# proj_konovalov_motor_driver.net
KiCad netlist of a schematic drawn in Altium Designer
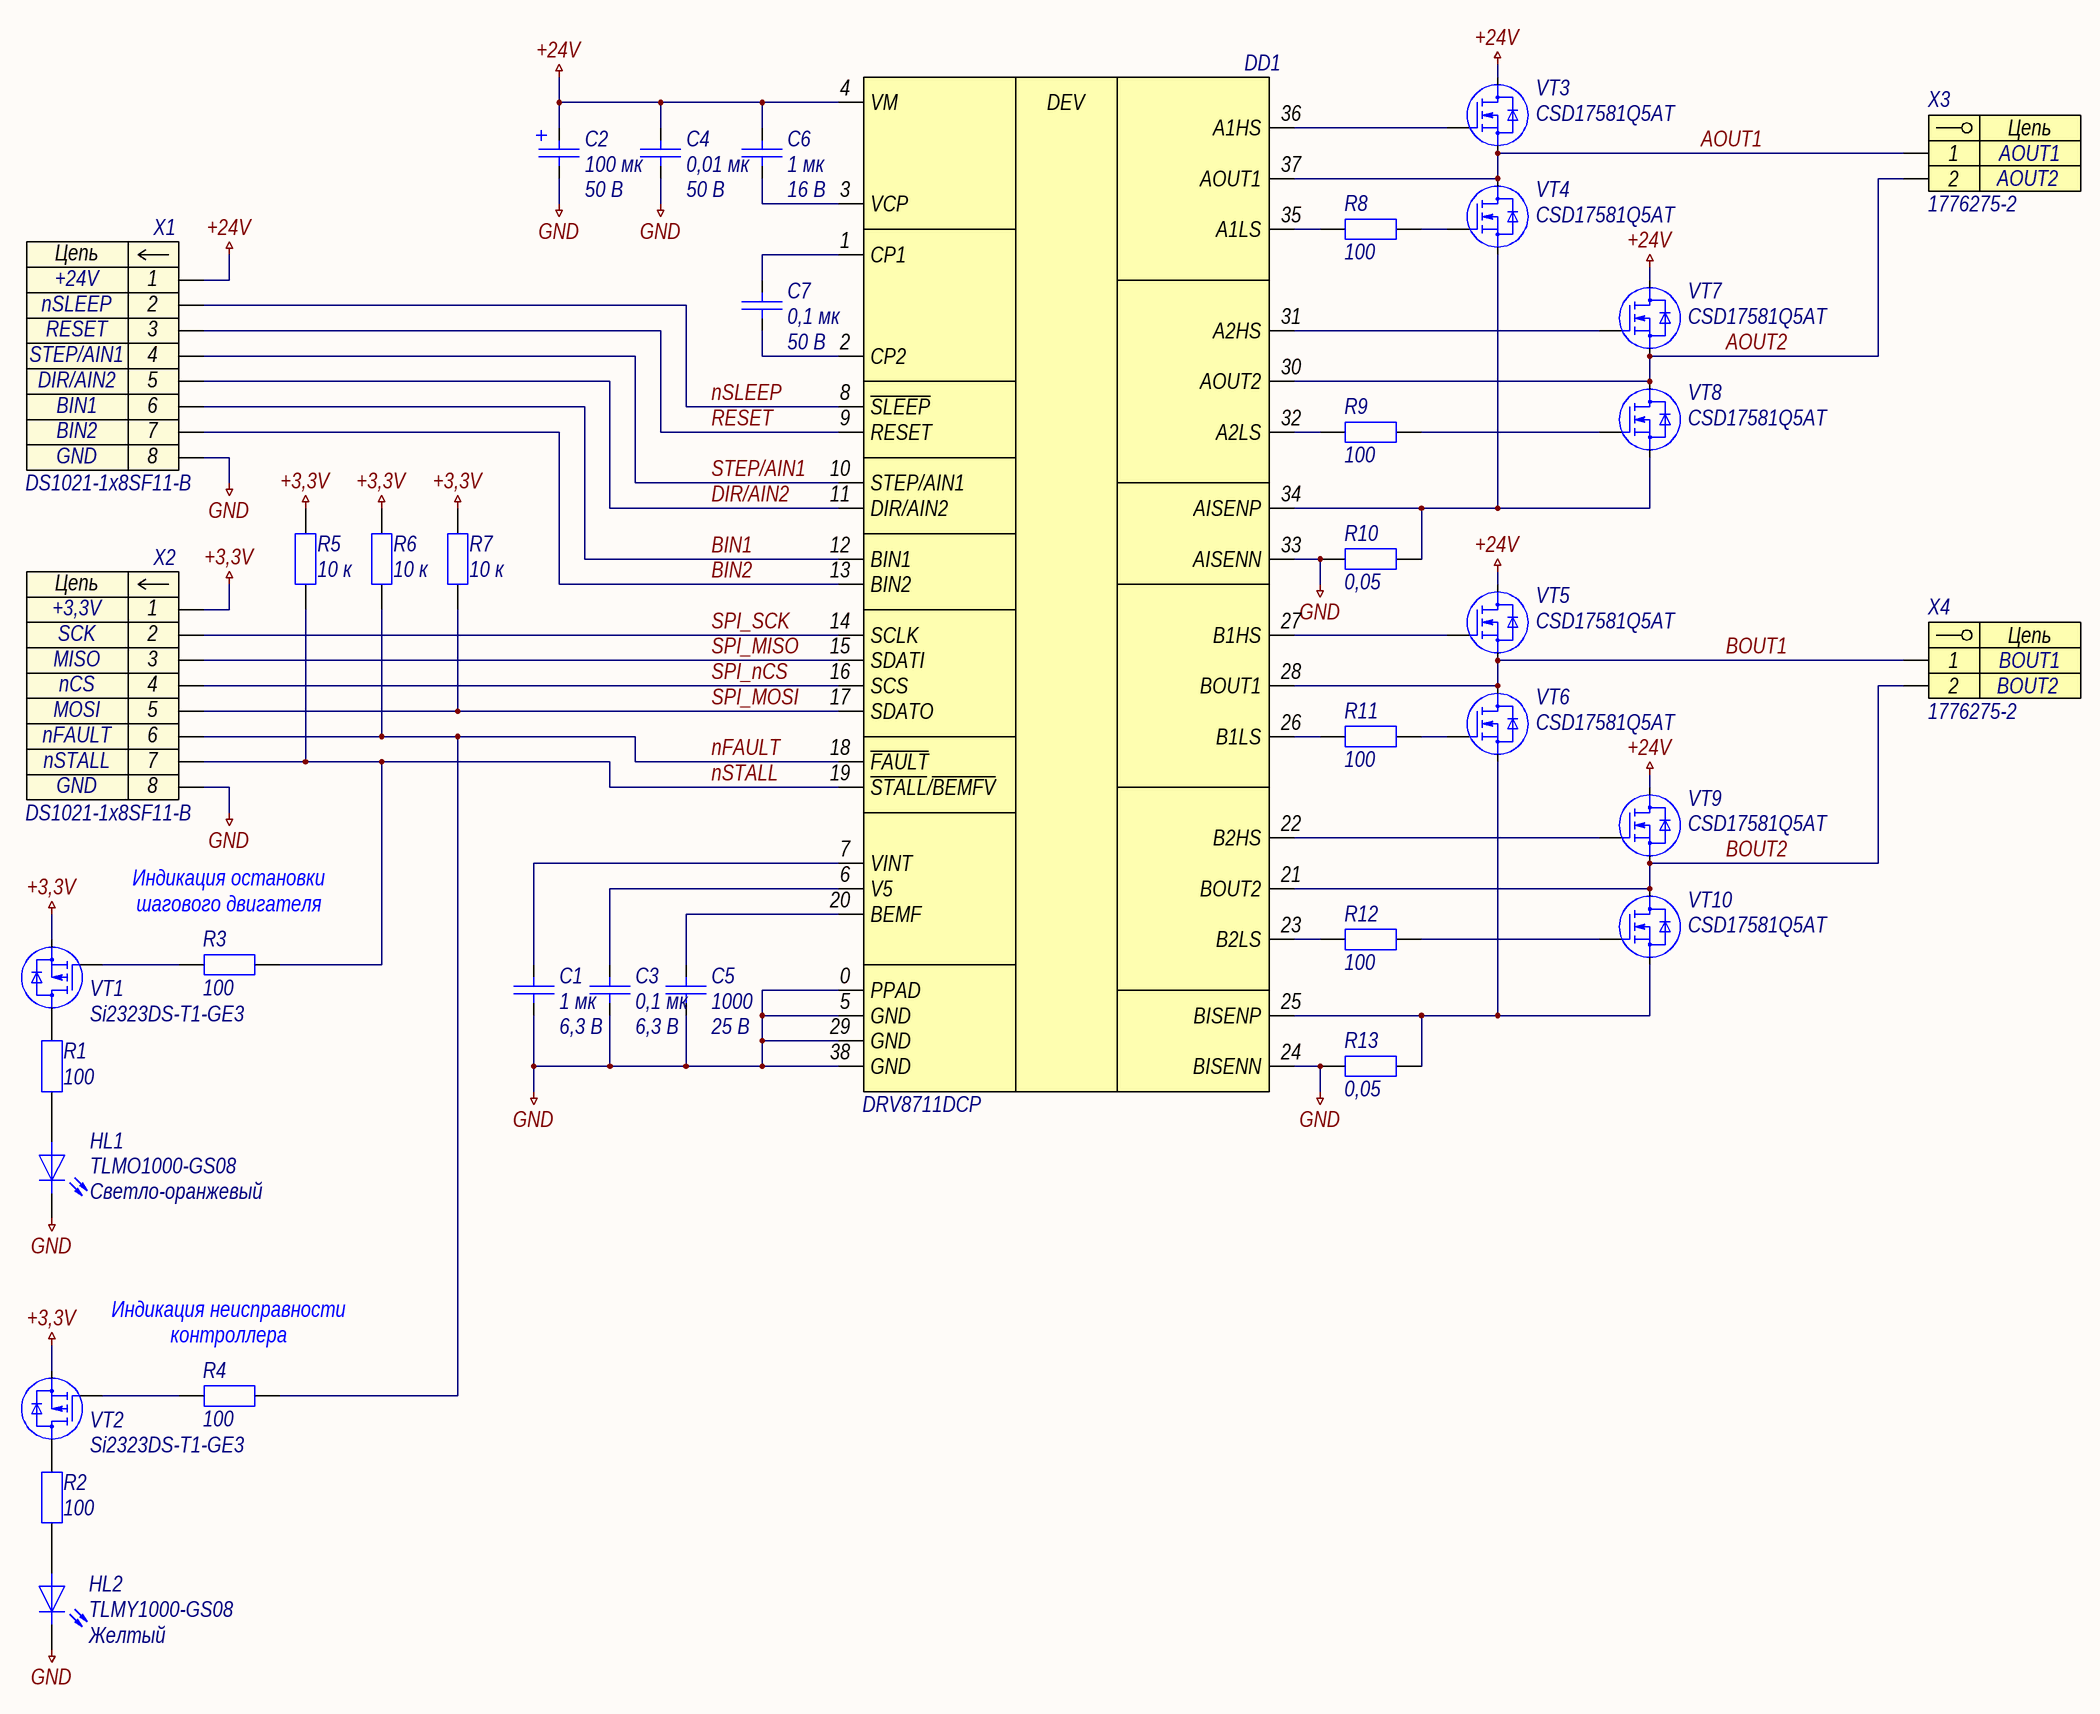
[diagram p0: proj_konovalov_motor_driver.SchDoc]

(export (version "E")
  (design (tool "Eeschema 10.0.6"))
  (components
    (comp (ref "C1")
      (value "1 мк")
      (footprint "C0603")
      (description "=Описание")
      (fields (field (name "НАПРЯЖЕНИЕ") "6,3 В"))
      (libsource (lib "Database_Students") (part "CAPACITOR-NONPOLAR"))
    )
    (comp (ref "C2")
      (value "100 мк")
      (footprint "CAPAE-660X660X800")
      (description "=Описание")
      (fields (field (name "НАПРЯЖЕНИЕ") "50 В"))
      (libsource (lib "Database_Students") (part "CAPACITOR-POLAR"))
    )
    (comp (ref "C3")
      (value "0,1 мк")
      (footprint "C0603")
      (description "=Описание")
      (fields (field (name "НАПРЯЖЕНИЕ") "6,3 В"))
      (libsource (lib "Database_Students") (part "CAPACITOR-NONPOLAR"))
    )
    (comp (ref "C4")
      (value "0,01 мк")
      (footprint "C0603")
      (description "=Описание")
      (fields (field (name "НАПРЯЖЕНИЕ") "50 В"))
      (libsource (lib "Database_Students") (part "CAPACITOR-NONPOLAR"))
    )
    (comp (ref "C5")
      (value "1000")
      (footprint "C0603")
      (description "=Описание")
      (fields (field (name "НАПРЯЖЕНИЕ") "25 В"))
      (libsource (lib "Database_Students") (part "CAPACITOR-NONPOLAR"))
    )
    (comp (ref "C6")
      (value "1 мк")
      (footprint "C0603")
      (description "=Описание")
      (fields (field (name "НАПРЯЖЕНИЕ") "16 В"))
      (libsource (lib "Database_Students") (part "CAPACITOR-NONPOLAR"))
    )
    (comp (ref "C7")
      (value "0,1 мк")
      (footprint "C0603")
      (description "=Описание")
      (fields (field (name "НАПРЯЖЕНИЕ") "50 В"))
      (libsource (lib "Database_Students") (part "CAPACITOR-NONPOLAR"))
    )
    (comp (ref "DD1")
      (value "DRV8711DCP")
      (footprint "HTSSOP-38-P50-470X290X120-L63X22-T470X290")
      (description "=Описание")
      (libsource (lib "Database_Students") (part "DRV8711DCP"))
    )
    (comp (ref "HL1")
      (value "TLMO1000-GS08")
      (footprint "HL0603")
      (description "=Описание")
      (fields (field (name "ЦВЕТ") "Светло-оранжевый"))
      (libsource (lib "Database_Students") (part "LED-COMMON"))
    )
    (comp (ref "HL2")
      (value "TLMY1000-GS08")
      (footprint "HL0603")
      (description "=Описание")
      (fields (field (name "ЦВЕТ") "Желтый"))
      (libsource (lib "Database_Students") (part "LED-COMMON"))
    )
    (comp (ref "R1")
      (value "100")
      (footprint "R0603")
      (description "=Описание")
      (libsource (lib "Database_Students") (part "RESISTOR-COMMON"))
    )
    (comp (ref "R2")
      (value "100")
      (footprint "R0603")
      (description "=Описание")
      (libsource (lib "Database_Students") (part "RESISTOR-COMMON"))
    )
    (comp (ref "R3")
      (value "100")
      (footprint "R0603")
      (description "=Описание")
      (libsource (lib "Database_Students") (part "RESISTOR-COMMON"))
    )
    (comp (ref "R4")
      (value "100")
      (footprint "R0603")
      (description "=Описание")
      (libsource (lib "Database_Students") (part "RESISTOR-COMMON"))
    )
    (comp (ref "R5")
      (value "10 к")
      (footprint "R0603")
      (description "=Описание")
      (libsource (lib "Database_Students") (part "RESISTOR-COMMON"))
    )
    (comp (ref "R6")
      (value "10 к")
      (footprint "R0603")
      (description "=Описание")
      (libsource (lib "Database_Students") (part "RESISTOR-COMMON"))
    )
    (comp (ref "R7")
      (value "10 к")
      (footprint "R0603")
      (description "=Описание")
      (libsource (lib "Database_Students") (part "RESISTOR-COMMON"))
    )
    (comp (ref "R8")
      (value "100")
      (footprint "R0603")
      (description "=Описание")
      (libsource (lib "Database_Students") (part "RESISTOR-COMMON"))
    )
    (comp (ref "R9")
      (value "100")
      (footprint "R0603")
      (description "=Описание")
      (libsource (lib "Database_Students") (part "RESISTOR-COMMON"))
    )
    (comp (ref "R10")
      (value "0,05")
      (footprint "R0603")
      (description "=Описание")
      (libsource (lib "Database_Students") (part "RESISTOR-COMMON"))
    )
    (comp (ref "R11")
      (value "100")
      (footprint "R0603")
      (description "=Описание")
      (libsource (lib "Database_Students") (part "RESISTOR-COMMON"))
    )
    (comp (ref "R12")
      (value "100")
      (footprint "R0603")
      (description "=Описание")
      (libsource (lib "Database_Students") (part "RESISTOR-COMMON"))
    )
    (comp (ref "R13")
      (value "0,05")
      (footprint "R0603")
      (description "=Описание")
      (libsource (lib "Database_Students") (part "RESISTOR-COMMON"))
    )
    (comp (ref "VT1")
      (value "Si2323DS-T1-GE3")
      (footprint "SOT-23-3-P95-292X237X112")
      (description "=Описание")
      (libsource (lib "Database_Students") (part "MOSFET-P-DIODE"))
    )
    (comp (ref "VT2")
      (value "Si2323DS-T1-GE3")
      (footprint "SOT-23-3-P95-292X237X112")
      (description "=Описание")
      (libsource (lib "Database_Students") (part "MOSFET-P-DIODE"))
    )
    (comp (ref "VT3")
      (value "CSD17581Q5AT")
      (footprint "VSONP-8-P127-600X500X110")
      (description "=Описание")
      (libsource (lib "Database_Students") (part "MOSFET-N-DIODE"))
    )
    (comp (ref "VT4")
      (value "CSD17581Q5AT")
      (footprint "VSONP-8-P127-600X500X110")
      (description "=Описание")
      (libsource (lib "Database_Students") (part "MOSFET-N-DIODE"))
    )
    (comp (ref "VT5")
      (value "CSD17581Q5AT")
      (footprint "VSONP-8-P127-600X500X110")
      (description "=Описание")
      (libsource (lib "Database_Students") (part "MOSFET-N-DIODE"))
    )
    (comp (ref "VT6")
      (value "CSD17581Q5AT")
      (footprint "VSONP-8-P127-600X500X110")
      (description "=Описание")
      (libsource (lib "Database_Students") (part "MOSFET-N-DIODE"))
    )
    (comp (ref "VT7")
      (value "CSD17581Q5AT")
      (footprint "VSONP-8-P127-600X500X110")
      (description "=Описание")
      (libsource (lib "Database_Students") (part "MOSFET-N-DIODE"))
    )
    (comp (ref "VT8")
      (value "CSD17581Q5AT")
      (footprint "VSONP-8-P127-600X500X110")
      (description "=Описание")
      (libsource (lib "Database_Students") (part "MOSFET-N-DIODE"))
    )
    (comp (ref "VT9")
      (value "CSD17581Q5AT")
      (footprint "VSONP-8-P127-600X500X110")
      (description "=Описание")
      (libsource (lib "Database_Students") (part "MOSFET-N-DIODE"))
    )
    (comp (ref "VT10")
      (value "CSD17581Q5AT")
      (footprint "VSONP-8-P127-600X500X110")
      (description "=Описание")
      (libsource (lib "Database_Students") (part "MOSFET-N-DIODE"))
    )
    (comp (ref "X1")
      (value "DS1021-1x8SF11-B")
      (footprint "DS1021-1X8SF11-B")
      (description "=Описание")
      (libsource (lib "Database_Students") (part "HEADER-8-PLG"))
    )
    (comp (ref "X2")
      (value "DS1021-1x8SF11-B")
      (footprint "DS1021-1X8SF11-B")
      (description "=Описание")
      (libsource (lib "Database_Students") (part "HEADER-8-PLG"))
    )
    (comp (ref "X3")
      (value "1776275-2")
      (footprint "1776275-2")
      (description "=Описание")
      (libsource (lib "Database_Students") (part "HEADER-2-TRM"))
    )
    (comp (ref "X4")
      (value "1776275-2")
      (footprint "1776275-2")
      (description "=Описание")
      (libsource (lib "Database_Students") (part "HEADER-2-TRM"))
    )
  )
  (nets
    (net (code "1") (name "+3,3V") (class "Default")
      (node (ref "R5") (pin "2") (pinfunction "2_2") (pintype "passive"))
      (node (ref "R6") (pin "2") (pinfunction "2_2") (pintype "passive"))
      (node (ref "R7") (pin "2") (pinfunction "2_2") (pintype "passive"))
      (node (ref "VT1") (pin "S") (pinfunction "S_S") (pintype "passive"))
      (node (ref "VT2") (pin "S") (pinfunction "S_S") (pintype "passive"))
      (node (ref "X2") (pin "1") (pinfunction "1_1") (pintype "passive"))
    )
    (net (code "2") (name "+24V") (class "Default")
      (node (ref "C2") (pin "1") (pinfunction "1_1") (pintype "passive"))
      (node (ref "C4") (pin "1") (pinfunction "1_1") (pintype "passive"))
      (node (ref "C6") (pin "1") (pinfunction "1_1") (pintype "passive"))
      (node (ref "DD1") (pin "4") (pinfunction "VM_4") (pintype "passive"))
      (node (ref "VT3") (pin "D") (pinfunction "D_D") (pintype "passive"))
      (node (ref "VT5") (pin "D") (pinfunction "D_D") (pintype "passive"))
      (node (ref "VT7") (pin "D") (pinfunction "D_D") (pintype "passive"))
      (node (ref "VT9") (pin "D") (pinfunction "D_D") (pintype "passive"))
      (node (ref "X1") (pin "1") (pinfunction "1_1") (pintype "passive"))
    )
    (net (code "3") (name "/AOUT1") (class "Default")
      (node (ref "DD1") (pin "37") (pinfunction "AOUT1_37") (pintype "passive"))
      (node (ref "VT3") (pin "S") (pinfunction "S_S") (pintype "passive"))
      (node (ref "VT4") (pin "D") (pinfunction "D_D") (pintype "passive"))
      (node (ref "X3") (pin "1") (pinfunction "1_1") (pintype "passive"))
    )
    (net (code "4") (name "/AOUT2") (class "Default")
      (node (ref "DD1") (pin "30") (pinfunction "AOUT2_30") (pintype "passive"))
      (node (ref "VT7") (pin "S") (pinfunction "S_S") (pintype "passive"))
      (node (ref "VT8") (pin "D") (pinfunction "D_D") (pintype "passive"))
      (node (ref "X3") (pin "2") (pinfunction "2_2") (pintype "passive"))
    )
    (net (code "5") (name "/BIN1") (class "Default")
      (node (ref "DD1") (pin "12") (pinfunction "BIN1_12") (pintype "passive"))
      (node (ref "X1") (pin "6") (pinfunction "6_6") (pintype "passive"))
    )
    (net (code "6") (name "/BIN2") (class "Default")
      (node (ref "DD1") (pin "13") (pinfunction "BIN2_13") (pintype "passive"))
      (node (ref "X1") (pin "7") (pinfunction "7_7") (pintype "passive"))
    )
    (net (code "7") (name "/BOUT1") (class "Default")
      (node (ref "DD1") (pin "28") (pinfunction "BOUT1_28") (pintype "passive"))
      (node (ref "VT5") (pin "S") (pinfunction "S_S") (pintype "passive"))
      (node (ref "VT6") (pin "D") (pinfunction "D_D") (pintype "passive"))
      (node (ref "X4") (pin "1") (pinfunction "1_1") (pintype "passive"))
    )
    (net (code "8") (name "/BOUT2") (class "Default")
      (node (ref "DD1") (pin "21") (pinfunction "BOUT2_21") (pintype "passive"))
      (node (ref "VT10") (pin "D") (pinfunction "D_D") (pintype "passive"))
      (node (ref "VT9") (pin "S") (pinfunction "S_S") (pintype "passive"))
      (node (ref "X4") (pin "2") (pinfunction "2_2") (pintype "passive"))
    )
    (net (code "9") (name "/DIR{slash}AIN2") (class "Default")
      (node (ref "DD1") (pin "11") (pinfunction "DIR/AIN2_11") (pintype "passive"))
      (node (ref "X1") (pin "5") (pinfunction "5_5") (pintype "passive"))
    )
    (net (code "10") (name "/RESET") (class "Default")
      (node (ref "DD1") (pin "9") (pinfunction "RESET_9") (pintype "passive"))
      (node (ref "X1") (pin "3") (pinfunction "3_3") (pintype "passive"))
    )
    (net (code "11") (name "/SPI_MISO") (class "Default")
      (node (ref "DD1") (pin "15") (pinfunction "SDATI_15") (pintype "passive"))
      (node (ref "X2") (pin "3") (pinfunction "3_3") (pintype "passive"))
    )
    (net (code "12") (name "/SPI_MOSI") (class "Default")
      (node (ref "DD1") (pin "17") (pinfunction "SDATO_17") (pintype "passive"))
      (node (ref "R7") (pin "1") (pinfunction "1_1") (pintype "passive"))
      (node (ref "X2") (pin "5") (pinfunction "5_5") (pintype "passive"))
    )
    (net (code "13") (name "/SPI_SCK") (class "Default")
      (node (ref "DD1") (pin "14") (pinfunction "SCLK_14") (pintype "passive"))
      (node (ref "X2") (pin "2") (pinfunction "2_2") (pintype "passive"))
    )
    (net (code "14") (name "/SPI_nCS") (class "Default")
      (node (ref "DD1") (pin "16") (pinfunction "SCS_16") (pintype "passive"))
      (node (ref "X2") (pin "4") (pinfunction "4_4") (pintype "passive"))
    )
    (net (code "15") (name "/STEP{slash}AIN1") (class "Default")
      (node (ref "DD1") (pin "10") (pinfunction "STEP/AIN1_10") (pintype "passive"))
      (node (ref "X1") (pin "4") (pinfunction "4_4") (pintype "passive"))
    )
    (net (code "16") (name "/nFAULT") (class "Default")
      (node (ref "DD1") (pin "18") (pinfunction "~{FAULT}_18") (pintype "passive"))
      (node (ref "R4") (pin "2") (pinfunction "2_2") (pintype "passive"))
      (node (ref "R6") (pin "1") (pinfunction "1_1") (pintype "passive"))
      (node (ref "X2") (pin "6") (pinfunction "6_6") (pintype "passive"))
    )
    (net (code "17") (name "/nSLEEP") (class "Default")
      (node (ref "DD1") (pin "8") (pinfunction "~{SLEEP}_8") (pintype "passive"))
      (node (ref "X1") (pin "2") (pinfunction "2_2") (pintype "passive"))
    )
    (net (code "18") (name "/nSTALL") (class "Default")
      (node (ref "DD1") (pin "19") (pinfunction "~{STALL}/~{BEMFV}_19") (pintype "passive"))
      (node (ref "R3") (pin "2") (pinfunction "2_2") (pintype "passive"))
      (node (ref "R5") (pin "1") (pinfunction "1_1") (pintype "passive"))
      (node (ref "X2") (pin "7") (pinfunction "7_7") (pintype "passive"))
    )
    (net (code "19") (name "GND") (class "Default")
      (node (ref "C1") (pin "2") (pinfunction "2_2") (pintype "passive"))
      (node (ref "C2") (pin "2") (pinfunction "2_2") (pintype "passive"))
      (node (ref "C3") (pin "2") (pinfunction "2_2") (pintype "passive"))
      (node (ref "C4") (pin "2") (pinfunction "2_2") (pintype "passive"))
      (node (ref "C5") (pin "2") (pinfunction "2_2") (pintype "passive"))
      (node (ref "DD1") (pin "0") (pinfunction "PPAD_0") (pintype "passive"))
      (node (ref "DD1") (pin "24") (pinfunction "BISENN_24") (pintype "passive"))
      (node (ref "DD1") (pin "29") (pinfunction "GND_29") (pintype "passive"))
      (node (ref "DD1") (pin "33") (pinfunction "AISENN_33") (pintype "passive"))
      (node (ref "DD1") (pin "38") (pinfunction "GND_38") (pintype "passive"))
      (node (ref "DD1") (pin "5") (pinfunction "GND_5") (pintype "passive"))
      (node (ref "HL1") (pin "1") (pinfunction "1_1") (pintype "passive"))
      (node (ref "HL2") (pin "1") (pinfunction "1_1") (pintype "passive"))
      (node (ref "R10") (pin "1") (pinfunction "1_1") (pintype "passive"))
      (node (ref "R13") (pin "1") (pinfunction "1_1") (pintype "passive"))
      (node (ref "X1") (pin "8") (pinfunction "8_8") (pintype "passive"))
      (node (ref "X2") (pin "8") (pinfunction "8_8") (pintype "passive"))
    )
    (net (code "20") (name "Net-(DD1-A1HS)") (class "Default")
      (node (ref "DD1") (pin "36") (pinfunction "A1HS_36") (pintype "passive"))
      (node (ref "VT3") (pin "G") (pinfunction "G_G") (pintype "passive"))
    )
    (net (code "21") (name "Net-(DD1-A1LS)") (class "Default")
      (node (ref "DD1") (pin "35") (pinfunction "A1LS_35") (pintype "passive"))
      (node (ref "R8") (pin "1") (pinfunction "1_1") (pintype "passive"))
    )
    (net (code "22") (name "Net-(DD1-A2HS)") (class "Default")
      (node (ref "DD1") (pin "31") (pinfunction "A2HS_31") (pintype "passive"))
      (node (ref "VT7") (pin "G") (pinfunction "G_G") (pintype "passive"))
    )
    (net (code "23") (name "Net-(DD1-A2LS)") (class "Default")
      (node (ref "DD1") (pin "32") (pinfunction "A2LS_32") (pintype "passive"))
      (node (ref "R9") (pin "1") (pinfunction "1_1") (pintype "passive"))
    )
    (net (code "24") (name "Net-(DD1-AISENP)") (class "Default")
      (node (ref "DD1") (pin "34") (pinfunction "AISENP_34") (pintype "passive"))
      (node (ref "R10") (pin "2") (pinfunction "2_2") (pintype "passive"))
      (node (ref "VT4") (pin "S") (pinfunction "S_S") (pintype "passive"))
      (node (ref "VT8") (pin "S") (pinfunction "S_S") (pintype "passive"))
    )
    (net (code "25") (name "Net-(DD1-B1HS)") (class "Default")
      (node (ref "DD1") (pin "27") (pinfunction "B1HS_27") (pintype "passive"))
      (node (ref "VT5") (pin "G") (pinfunction "G_G") (pintype "passive"))
    )
    (net (code "26") (name "Net-(DD1-B1LS)") (class "Default")
      (node (ref "DD1") (pin "26") (pinfunction "B1LS_26") (pintype "passive"))
      (node (ref "R11") (pin "1") (pinfunction "1_1") (pintype "passive"))
    )
    (net (code "27") (name "Net-(DD1-B2HS)") (class "Default")
      (node (ref "DD1") (pin "22") (pinfunction "B2HS_22") (pintype "passive"))
      (node (ref "VT9") (pin "G") (pinfunction "G_G") (pintype "passive"))
    )
    (net (code "28") (name "Net-(DD1-B2LS)") (class "Default")
      (node (ref "DD1") (pin "23") (pinfunction "B2LS_23") (pintype "passive"))
      (node (ref "R12") (pin "1") (pinfunction "1_1") (pintype "passive"))
    )
    (net (code "29") (name "Net-(DD1-BEMF)") (class "Default")
      (node (ref "C5") (pin "1") (pinfunction "1_1") (pintype "passive"))
      (node (ref "DD1") (pin "20") (pinfunction "BEMF_20") (pintype "passive"))
    )
    (net (code "30") (name "Net-(DD1-BISENP)") (class "Default")
      (node (ref "DD1") (pin "25") (pinfunction "BISENP_25") (pintype "passive"))
      (node (ref "R13") (pin "2") (pinfunction "2_2") (pintype "passive"))
      (node (ref "VT10") (pin "S") (pinfunction "S_S") (pintype "passive"))
      (node (ref "VT6") (pin "S") (pinfunction "S_S") (pintype "passive"))
    )
    (net (code "31") (name "Net-(DD1-CP1)") (class "Default")
      (node (ref "C7") (pin "1") (pinfunction "1_1") (pintype "passive"))
      (node (ref "DD1") (pin "1") (pinfunction "CP1_1") (pintype "passive"))
    )
    (net (code "32") (name "Net-(DD1-CP2)") (class "Default")
      (node (ref "C7") (pin "2") (pinfunction "2_2") (pintype "passive"))
      (node (ref "DD1") (pin "2") (pinfunction "CP2_2") (pintype "passive"))
    )
    (net (code "33") (name "Net-(DD1-V5)") (class "Default")
      (node (ref "C3") (pin "1") (pinfunction "1_1") (pintype "passive"))
      (node (ref "DD1") (pin "6") (pinfunction "V5_6") (pintype "passive"))
    )
    (net (code "34") (name "Net-(DD1-VCP)") (class "Default")
      (node (ref "C6") (pin "2") (pinfunction "2_2") (pintype "passive"))
      (node (ref "DD1") (pin "3") (pinfunction "VCP_3") (pintype "passive"))
    )
    (net (code "35") (name "Net-(DD1-VINT)") (class "Default")
      (node (ref "C1") (pin "1") (pinfunction "1_1") (pintype "passive"))
      (node (ref "DD1") (pin "7") (pinfunction "VINT_7") (pintype "passive"))
    )
    (net (code "36") (name "Net-(HL1-Pad2)") (class "Default")
      (node (ref "HL1") (pin "2") (pinfunction "2_2") (pintype "passive"))
      (node (ref "R1") (pin "1") (pinfunction "1_1") (pintype "passive"))
    )
    (net (code "37") (name "Net-(HL2-Pad2)") (class "Default")
      (node (ref "HL2") (pin "2") (pinfunction "2_2") (pintype "passive"))
      (node (ref "R2") (pin "1") (pinfunction "1_1") (pintype "passive"))
    )
    (net (code "38") (name "Net-(R1-Pad2)") (class "Default")
      (node (ref "R1") (pin "2") (pinfunction "2_2") (pintype "passive"))
      (node (ref "VT1") (pin "D") (pinfunction "D_D") (pintype "passive"))
    )
    (net (code "39") (name "Net-(R2-Pad2)") (class "Default")
      (node (ref "R2") (pin "2") (pinfunction "2_2") (pintype "passive"))
      (node (ref "VT2") (pin "D") (pinfunction "D_D") (pintype "passive"))
    )
    (net (code "40") (name "Net-(R3-Pad1)") (class "Default")
      (node (ref "R3") (pin "1") (pinfunction "1_1") (pintype "passive"))
      (node (ref "VT1") (pin "G") (pinfunction "G_G") (pintype "passive"))
    )
    (net (code "41") (name "Net-(R4-Pad1)") (class "Default")
      (node (ref "R4") (pin "1") (pinfunction "1_1") (pintype "passive"))
      (node (ref "VT2") (pin "G") (pinfunction "G_G") (pintype "passive"))
    )
    (net (code "42") (name "Net-(R8-Pad2)") (class "Default")
      (node (ref "R8") (pin "2") (pinfunction "2_2") (pintype "passive"))
      (node (ref "VT4") (pin "G") (pinfunction "G_G") (pintype "passive"))
    )
    (net (code "43") (name "Net-(R9-Pad2)") (class "Default")
      (node (ref "R9") (pin "2") (pinfunction "2_2") (pintype "passive"))
      (node (ref "VT8") (pin "G") (pinfunction "G_G") (pintype "passive"))
    )
    (net (code "44") (name "Net-(R11-Pad2)") (class "Default")
      (node (ref "R11") (pin "2") (pinfunction "2_2") (pintype "passive"))
      (node (ref "VT6") (pin "G") (pinfunction "G_G") (pintype "passive"))
    )
    (net (code "45") (name "Net-(R12-Pad2)") (class "Default")
      (node (ref "R12") (pin "2") (pinfunction "2_2") (pintype "passive"))
      (node (ref "VT10") (pin "G") (pinfunction "G_G") (pintype "passive"))
    )
  )
)
